# V3s.net
KiCad netlist of a schematic drawn in Altium Designer
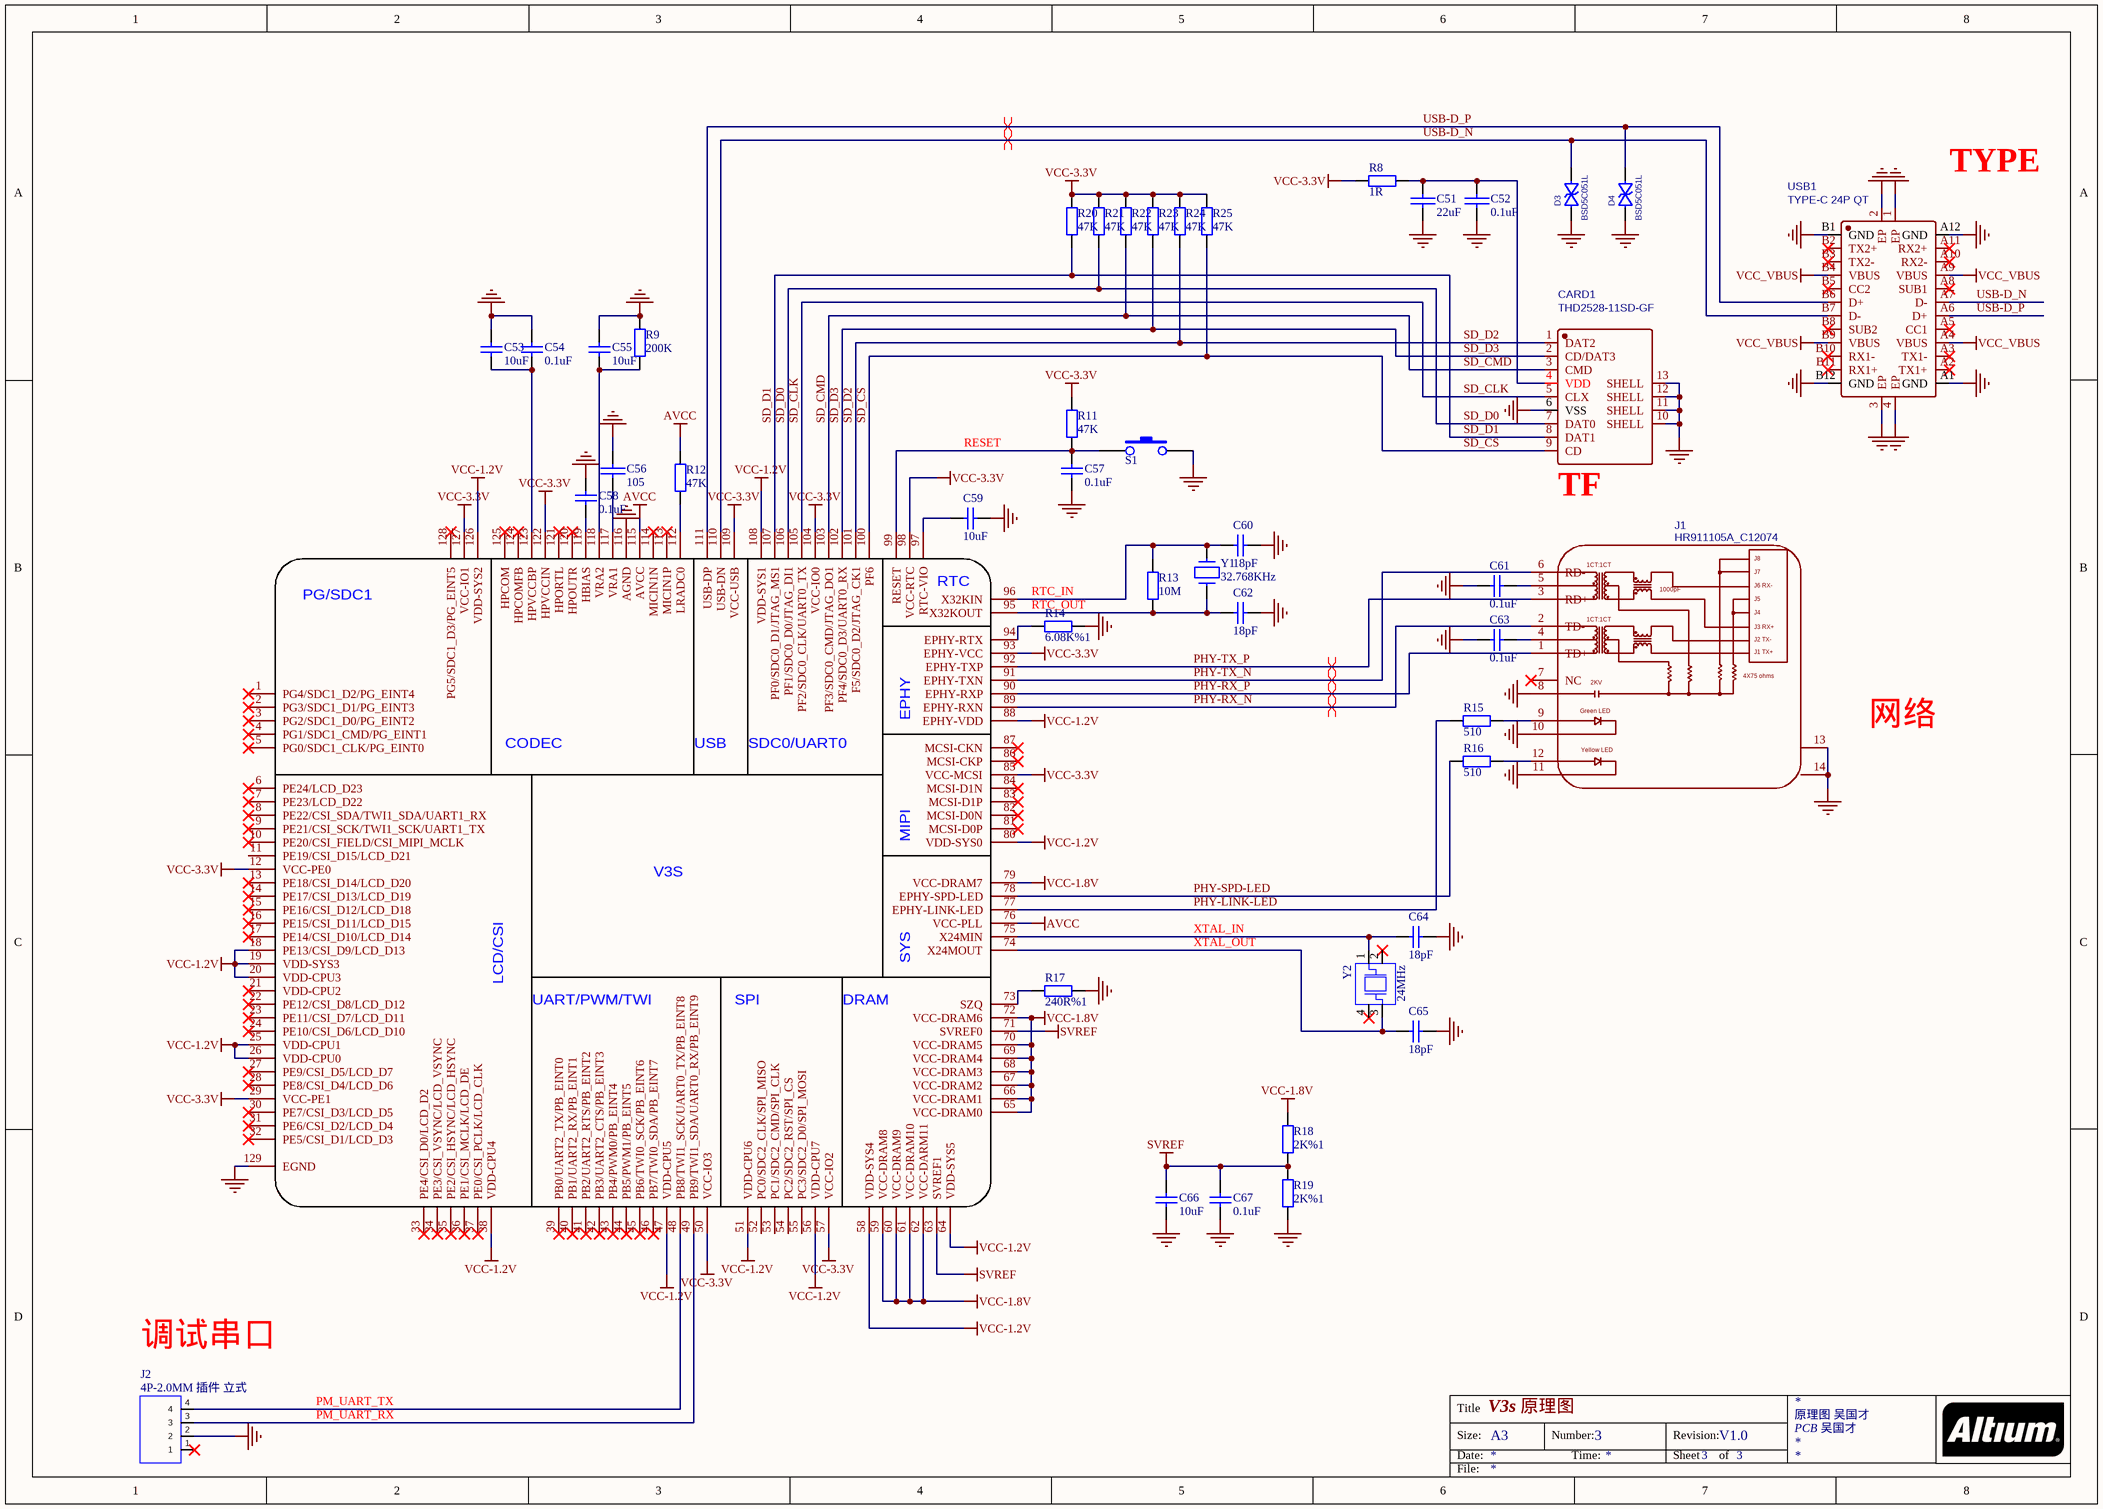
[diagram p0: V3s.SchDoc]

(export (version "E")
  (design (tool "Eeschema 10.0.6"))
  (components
    (comp (ref "C51")
      (value "22uF")
      (footprint "0805_C")
      (description "贴片电容")
      (libsource (lib "*") (part "CAP"))
    )
    (comp (ref "C52")
      (value "0.1uF")
      (footprint "0402_C")
      (description "贴片电容")
      (libsource (lib "*") (part "CAP"))
    )
    (comp (ref "C53")
      (value "10uF")
      (footprint "0603_C")
      (description "贴片电容")
      (libsource (lib "LSD") (part "CAP-SMD"))
    )
    (comp (ref "C54")
      (value "0.1uF")
      (footprint "0402_C")
      (description "贴片电容")
      (libsource (lib "LSD") (part "CAP-SMD"))
    )
    (comp (ref "C55")
      (value "10uF")
      (footprint "0603_C")
      (description "贴片电容")
      (libsource (lib "LSD") (part "CAP-SMD"))
    )
    (comp (ref "C56")
      (value "105")
      (footprint "0402_C")
      (description "贴片电容")
      (libsource (lib "*") (part "CAP"))
    )
    (comp (ref "C57")
      (value "0.1uF")
      (footprint "0402_C")
      (description "贴片电容")
      (libsource (lib "LSD") (part "CAP-SMD"))
    )
    (comp (ref "C58")
      (value "0.1uF")
      (footprint "0402_C")
      (description "贴片电容")
      (libsource (lib "LSD") (part "CAP-SMD"))
    )
    (comp (ref "C59")
      (value "10uF")
      (footprint "0603_C")
      (description "贴片电容")
      (libsource (lib "LSD") (part "CAP-SMD"))
    )
    (comp (ref "C60")
      (value "18pF")
      (footprint "0402_C")
      (description "贴片电容")
      (libsource (lib "电容") (part "CAP-SMD"))
    )
    (comp (ref "C61")
      (value "0.1uF")
      (footprint "0603_C")
      (description "贴片电容")
      (libsource (lib "LSD") (part "CAP-SMD"))
    )
    (comp (ref "C62")
      (value "18pF")
      (footprint "0402_C")
      (description "贴片电容")
      (libsource (lib "电容") (part "CAP-SMD"))
    )
    (comp (ref "C63")
      (value "0.1uF")
      (footprint "0603_C")
      (description "贴片电容")
      (libsource (lib "LSD") (part "CAP-SMD"))
    )
    (comp (ref "C64")
      (value "18pF")
      (footprint "0402_C")
      (description "贴片电容")
      (libsource (lib "LSD") (part "CAP-SMD"))
    )
    (comp (ref "C65")
      (value "18pF")
      (footprint "0402_C")
      (description "贴片电容")
      (libsource (lib "LSD") (part "CAP-SMD"))
    )
    (comp (ref "C66")
      (value "10uF")
      (footprint "0603_C")
      (description "贴片电容")
      (libsource (lib "LSD") (part "CAP-SMD"))
    )
    (comp (ref "C67")
      (value "0.1uF")
      (footprint "0402_C")
      (description "贴片电容")
      (libsource (lib "LSD") (part "CAP-SMD"))
    )
    (comp (ref "CARD1")
      (value "THD2528-11SD-GF")
      (footprint "TF-CARD-14.5X14.75X1.85MM")
      (fields (field (name "BOM_SUPPLIER PART") "C283232") (field (name "CONTRIBUTOR") "LCSC"))
      (libsource (lib "altium-import") (part "root_0_THD2528-11SD-GF_"))
    )
    (comp (ref "D3") (value "BSD5C051L") (footprint "SOD-523") (libsource (lib "*") (part "DIODE_ESD")))
    (comp (ref "D4") (value "BSD5C051L") (footprint "SOD-523") (libsource (lib "*") (part "DIODE_ESD")))
    (comp (ref "J1")
      (value "HR911105A_C12074")
      (footprint "HR913550A")
      (fields (field (name "BOM_MANUFACTURER PART") "HR911105A") (field (name "BOM_SUPPLIER PART") "C12074"))
      (libsource (lib "altium-import") (part "root_0_HR911105A_C12074_"))
    )
    (comp (ref "J2")
      (value "4P-2.0MM 插件 立式")
      (footprint "Hole,4P=2.00MM")
      (description "插件-立式插座")
      (fields (field (name "SOURCE_PATH") "E:\\JIANG\\二代产品开发资料\\设计参考\\A20CORNEL\\LIBRARY1.OLB"))
      (libsource (lib "*") (part "CON-4P"))
    )
    (comp (ref "R8")
      (value "1R")
      (footprint "0402_R")
      (description "贴片电阻")
      (libsource (lib "") (part "Res2_2"))
    )
    (comp (ref "R9")
      (value "200K")
      (footprint "0402_R")
      (description "贴片电阻")
      (libsource (lib "") (part "Res2_3"))
    )
    (comp (ref "R11")
      (value "47K")
      (footprint "0402_R")
      (description "贴片电阻")
      (libsource (lib "*") (part "Res2"))
    )
    (comp (ref "R12")
      (value "47K")
      (footprint "0402_R")
      (description "贴片电阻")
      (libsource (lib "*") (part "Res2"))
    )
    (comp (ref "R13")
      (value "10M")
      (footprint "0402_R")
      (description "贴片电阻")
      (libsource (lib "") (part "Res2_2"))
    )
    (comp (ref "R14")
      (value "6.08K%1")
      (footprint "0402_R")
      (description "贴片电阻")
      (libsource (lib "") (part "Res2_2"))
    )
    (comp (ref "R15")
      (value "510")
      (footprint "0402_R")
      (description "贴片电阻")
      (libsource (lib "") (part "Res2_1"))
    )
    (comp (ref "R16")
      (value "510")
      (footprint "0402_R")
      (description "贴片电阻")
      (libsource (lib "") (part "Res2_1"))
    )
    (comp (ref "R17")
      (value "240R%1")
      (footprint "0402_R")
      (description "贴片电阻")
      (libsource (lib "") (part "Res2_2"))
    )
    (comp (ref "R18")
      (value "2K%1")
      (footprint "0402_R")
      (description "贴片电阻")
      (libsource (lib "*") (part "Res2"))
    )
    (comp (ref "R19")
      (value "2K%1")
      (footprint "0402_R")
      (description "贴片电阻")
      (libsource (lib "*") (part "Res2"))
    )
    (comp (ref "R20")
      (value "47K")
      (footprint "0402_R")
      (description "贴片电阻")
      (libsource (lib "*") (part "Res2"))
    )
    (comp (ref "R21")
      (value "47K")
      (footprint "0402_R")
      (description "贴片电阻")
      (libsource (lib "*") (part "Res2"))
    )
    (comp (ref "R22")
      (value "47K")
      (footprint "0402_R")
      (description "贴片电阻")
      (libsource (lib "*") (part "Res2"))
    )
    (comp (ref "R23")
      (value "47K")
      (footprint "0402_R")
      (description "贴片电阻")
      (libsource (lib "*") (part "Res2"))
    )
    (comp (ref "R24")
      (value "47K")
      (footprint "0402_R")
      (description "贴片电阻")
      (libsource (lib "*") (part "Res2"))
    )
    (comp (ref "R25")
      (value "47K")
      (footprint "0402_R")
      (description "贴片电阻")
      (libsource (lib "*") (part "Res2"))
    )
    (comp (ref "S1") (value "SW-PB_1") (footprint "KEY-3X6-SMD") (libsource (lib "Devices") (part "SW-PB_1")))
    (comp (ref "USB1")
      (value "TYPE-C 24P QT")
      (footprint "USB-C-SMD_TYPE-C-24P-QT")
      (description "C2681555 品牌： SHOU HAN(首韩)")
      (fields (field (name "BOM_SUPPLIER PART") "C2681555") (field (name "CONTRIBUTOR") "LCSC"))
      (libsource (lib "altium-import") (part "root_0_TYPE-C 24P QT_"))
    )
    (comp (ref "V1")
      (value "V3S")
      (footprint "QUAD128")
      (fields (field (name "CONTRIBUTOR") "cnicfhnui"))
      (libsource (lib "altium-import") (part "root_0_V3S_"))
    )
    (comp (ref "Y1")
      (value "32.768KHz")
      (footprint "SMD3215-2P")
      (description "时钟晶体 32.768kHz 12.5PF 20PPM")
      (libsource (lib "晶振") (part "CRYSTAL-C"))
    )
    (comp (ref "Y2")
      (value "24MHz")
      (footprint "SMD3225-4P")
      (description "贴片无源晶振")
      (libsource (lib "*") (part "CRYSTAL4P_2"))
    )
  )
  (nets
    (net (code "1") (name "/PHY-LINK-LED") (class "Default")
      (node (ref "R15") (pin "2") (pinfunction "2_2") (pintype "passive"))
      (node (ref "V1") (pin "77") (pinfunction "EPHY-LINK-LED_77") (pintype "passive"))
    )
    (net (code "2") (name "/PHY-RX_N") (class "Default")
      (node (ref "J1") (pin "2") (pinfunction "TD-_2") (pintype "passive"))
      (node (ref "V1") (pin "89") (pinfunction "EPHY-RXN_89") (pintype "passive"))
    )
    (net (code "3") (name "/PHY-RX_P") (class "Default")
      (node (ref "J1") (pin "1") (pinfunction "TD+_1") (pintype "passive"))
      (node (ref "V1") (pin "90") (pinfunction "EPHY-RXP_90") (pintype "passive"))
    )
    (net (code "4") (name "/PHY-SPD-LED") (class "Default")
      (node (ref "R16") (pin "2") (pinfunction "2_2") (pintype "passive"))
      (node (ref "V1") (pin "78") (pinfunction "EPHY-SPD-LED_78") (pintype "passive"))
    )
    (net (code "5") (name "/PHY-TX_N") (class "Default")
      (node (ref "J1") (pin "6") (pinfunction "RD-_6") (pintype "passive"))
      (node (ref "V1") (pin "91") (pinfunction "EPHY-TXN_91") (pintype "passive"))
    )
    (net (code "6") (name "/PHY-TX_P") (class "Default")
      (node (ref "J1") (pin "3") (pinfunction "RD+_3") (pintype "passive"))
      (node (ref "V1") (pin "92") (pinfunction "EPHY-TXP_92") (pintype "passive"))
    )
    (net (code "7") (name "/PM_UART_RX") (class "Default")
      (node (ref "J2") (pin "3") (pinfunction "3_3") (pintype "passive"))
      (node (ref "V1") (pin "49") (pinfunction "PB9/TWI1_SDA/UART0_RX/PB_EINT9_49") (pintype "passive"))
    )
    (net (code "8") (name "/PM_UART_TX") (class "Default")
      (node (ref "J2") (pin "4") (pinfunction "4_4") (pintype "passive"))
      (node (ref "V1") (pin "48") (pinfunction "PB8/TWI1_SCK/UART0_TX/PB_EINT8_48") (pintype "passive"))
    )
    (net (code "9") (name "/RESET") (class "Default")
      (node (ref "C57") (pin "1") (pintype "passive"))
      (node (ref "R11") (pin "2") (pinfunction "2_2") (pintype "passive"))
      (node (ref "S1") (pin "2") (pinfunction "2_2") (pintype "passive"))
      (node (ref "V1") (pin "99") (pinfunction "RESET_99") (pintype "passive"))
    )
    (net (code "10") (name "/RTC_IN") (class "Default")
      (node (ref "C60") (pin "1") (pintype "passive"))
      (node (ref "R13") (pin "2") (pinfunction "2_2") (pintype "passive"))
      (node (ref "V1") (pin "96") (pinfunction "X32KIN_96") (pintype "passive"))
      (node (ref "Y1") (pin "2") (pinfunction "2_2") (pintype "passive"))
    )
    (net (code "11") (name "/RTC_OUT") (class "Default")
      (node (ref "C62") (pin "1") (pintype "passive"))
      (node (ref "R13") (pin "1") (pinfunction "1_1") (pintype "passive"))
      (node (ref "V1") (pin "95") (pinfunction "X32KOUT_95") (pintype "passive"))
      (node (ref "Y1") (pin "1") (pinfunction "1_1") (pintype "passive"))
    )
    (net (code "12") (name "/SD_CLK") (class "Default")
      (node (ref "CARD1") (pin "5") (pinfunction "CLX_5") (pintype "passive"))
      (node (ref "V1") (pin "105") (pinfunction "PF2/SDC0_CLK/UART0_TX_105") (pintype "passive"))
    )
    (net (code "13") (name "/SD_CMD") (class "Default")
      (node (ref "CARD1") (pin "3") (pinfunction "CMD_3") (pintype "passive"))
      (node (ref "R22") (pin "2") (pinfunction "2_2") (pintype "passive"))
      (node (ref "V1") (pin "103") (pinfunction "PF3/SDC0_CMD/JTAG_DO1_103") (pintype "passive"))
    )
    (net (code "14") (name "/SD_CS") (class "Default")
      (node (ref "CARD1") (pin "9") (pinfunction "CD_9") (pintype "passive"))
      (node (ref "R25") (pin "2") (pinfunction "2_2") (pintype "passive"))
      (node (ref "V1") (pin "100") (pinfunction "PF6_100") (pintype "passive"))
    )
    (net (code "15") (name "/SD_D0") (class "Default")
      (node (ref "CARD1") (pin "7") (pinfunction "DAT0_7") (pintype "passive"))
      (node (ref "R21") (pin "2") (pinfunction "2_2") (pintype "passive"))
      (node (ref "V1") (pin "106") (pinfunction "PF1/SDC0_D0/JTAG_DI1_106") (pintype "passive"))
    )
    (net (code "16") (name "/SD_D1") (class "Default")
      (node (ref "CARD1") (pin "8") (pinfunction "DAT1_8") (pintype "passive"))
      (node (ref "R20") (pin "2") (pinfunction "2_2") (pintype "passive"))
      (node (ref "V1") (pin "107") (pinfunction "PF0/SDC0_D1/JTAG_MS1_107") (pintype "passive"))
    )
    (net (code "17") (name "/SD_D2") (class "Default")
      (node (ref "CARD1") (pin "1") (pinfunction "DAT2_1") (pintype "passive"))
      (node (ref "R24") (pin "2") (pinfunction "2_2") (pintype "passive"))
      (node (ref "V1") (pin "101") (pinfunction "F5/SDC0_D2/JTAG_CK1_101") (pintype "passive"))
    )
    (net (code "18") (name "/SD_D3") (class "Default")
      (node (ref "CARD1") (pin "2") (pinfunction "CD/DAT3_2") (pintype "passive"))
      (node (ref "R23") (pin "2") (pinfunction "2_2") (pintype "passive"))
      (node (ref "V1") (pin "102") (pinfunction "PF4/SDC0_D3/UART0_RX_102") (pintype "passive"))
    )
    (net (code "19") (name "/USB-D_N") (class "Default")
      (node (ref "D3") (pin "2") (pinfunction "2_2") (pintype "passive"))
      (node (ref "USB1") (pin "A7") (pinfunction "D-_A7") (pintype "passive"))
      (node (ref "USB1") (pin "B7") (pinfunction "D-_B7") (pintype "passive"))
      (node (ref "V1") (pin "110") (pinfunction "USB-DN_110") (pintype "passive"))
    )
    (net (code "20") (name "/USB-D_P") (class "Default")
      (node (ref "D4") (pin "2") (pinfunction "2_2") (pintype "passive"))
      (node (ref "USB1") (pin "A6") (pinfunction "D+_A6") (pintype "passive"))
      (node (ref "USB1") (pin "B6") (pinfunction "D+_B6") (pintype "passive"))
      (node (ref "V1") (pin "111") (pinfunction "USB-DP_111") (pintype "passive"))
    )
    (net (code "21") (name "/XTAL_IN") (class "Default")
      (node (ref "C64") (pin "2") (pintype "passive"))
      (node (ref "V1") (pin "75") (pinfunction "X24MIN_75") (pintype "passive"))
      (node (ref "Y2") (pin "1") (pinfunction "CIN_1") (pintype "passive"))
    )
    (net (code "22") (name "/XTAL_OUT") (class "Default")
      (node (ref "C65") (pin "2") (pintype "passive"))
      (node (ref "V1") (pin "74") (pinfunction "X24MOUT_74") (pintype "passive"))
      (node (ref "Y2") (pin "3") (pinfunction "COUT_3") (pintype "passive"))
    )
    (net (code "23") (name "AVCC") (class "Default")
      (node (ref "R12") (pin "1") (pinfunction "1_1") (pintype "passive"))
      (node (ref "V1") (pin "115") (pinfunction "AVCC_115") (pintype "passive"))
      (node (ref "V1") (pin "76") (pinfunction "VCC-PLL_76") (pintype "passive"))
    )
    (net (code "24") (name "GND") (class "Default")
      (node (ref "C51") (pin "1") (pintype "passive"))
      (node (ref "C52") (pin "1") (pintype "passive"))
      (node (ref "C53") (pin "2") (pintype "passive"))
      (node (ref "C54") (pin "1") (pintype "passive"))
      (node (ref "C55") (pin "2") (pintype "passive"))
      (node (ref "C56") (pin "2") (pintype "passive"))
      (node (ref "C57") (pin "2") (pintype "passive"))
      (node (ref "C58") (pin "1") (pintype "passive"))
      (node (ref "C59") (pin "2") (pintype "passive"))
      (node (ref "C60") (pin "2") (pintype "passive"))
      (node (ref "C61") (pin "2") (pintype "passive"))
      (node (ref "C62") (pin "2") (pintype "passive"))
      (node (ref "C63") (pin "2") (pintype "passive"))
      (node (ref "C64") (pin "1") (pintype "passive"))
      (node (ref "C65") (pin "1") (pintype "passive"))
      (node (ref "C66") (pin "2") (pintype "passive"))
      (node (ref "C67") (pin "2") (pintype "passive"))
      (node (ref "CARD1") (pin "10") (pinfunction "SHELL_10") (pintype "passive"))
      (node (ref "CARD1") (pin "11") (pinfunction "SHELL_11") (pintype "passive"))
      (node (ref "CARD1") (pin "12") (pinfunction "SHELL_12") (pintype "passive"))
      (node (ref "CARD1") (pin "13") (pinfunction "SHELL_13") (pintype "passive"))
      (node (ref "CARD1") (pin "6") (pinfunction "VSS_6") (pintype "passive"))
      (node (ref "D3") (pin "1") (pinfunction "1_1") (pintype "passive"))
      (node (ref "D4") (pin "1") (pinfunction "1_1") (pintype "passive"))
      (node (ref "J1") (pin "10") (pinfunction "10_10") (pintype "passive"))
      (node (ref "J1") (pin "11") (pinfunction "11_11") (pintype "passive"))
      (node (ref "J1") (pin "13") (pinfunction "SH1_13") (pintype "passive"))
      (node (ref "J1") (pin "14") (pinfunction "SH2_14") (pintype "passive"))
      (node (ref "J1") (pin "8") (pinfunction "CHS_GND_8") (pintype "passive"))
      (node (ref "J2") (pin "2") (pinfunction "2_2") (pintype "passive"))
      (node (ref "R14") (pin "2") (pinfunction "2_2") (pintype "passive"))
      (node (ref "R17") (pin "2") (pinfunction "2_2") (pintype "passive"))
      (node (ref "R19") (pin "2") (pinfunction "2_2") (pintype "passive"))
      (node (ref "R9") (pin "2") (pinfunction "2_2") (pintype "passive"))
      (node (ref "S1") (pin "1") (pinfunction "1_1") (pintype "passive"))
      (node (ref "USB1") (pin "1") (pinfunction "EP_1") (pintype "passive"))
      (node (ref "USB1") (pin "2") (pinfunction "EP_2") (pintype "passive"))
      (node (ref "USB1") (pin "3") (pinfunction "EP_3") (pintype "passive"))
      (node (ref "USB1") (pin "4") (pinfunction "EP_4") (pintype "passive"))
      (node (ref "USB1") (pin "A1") (pinfunction "GND_A1") (pintype "passive"))
      (node (ref "USB1") (pin "A12") (pinfunction "GND_A12") (pintype "passive"))
      (node (ref "USB1") (pin "B1") (pinfunction "GND_B1") (pintype "passive"))
      (node (ref "USB1") (pin "B12") (pinfunction "GND_B12") (pintype "passive"))
      (node (ref "V1") (pin "116") (pinfunction "AGND_116") (pintype "passive"))
      (node (ref "V1") (pin "129") (pinfunction "EGND_129") (pintype "passive"))
    )
    (net (code "25") (name "Net-(C61-Pad1)") (class "Default")
      (node (ref "C61") (pin "1") (pintype "passive"))
      (node (ref "J1") (pin "5") (pinfunction "5_5") (pintype "passive"))
    )
    (net (code "26") (name "Net-(C63-Pad1)") (class "Default")
      (node (ref "C63") (pin "1") (pintype "passive"))
      (node (ref "J1") (pin "4") (pinfunction "4_4") (pintype "passive"))
    )
    (net (code "27") (name "Net-(CARD1-VDD)") (class "Default")
      (node (ref "C51") (pin "2") (pintype "passive"))
      (node (ref "C52") (pin "2") (pintype "passive"))
      (node (ref "CARD1") (pin "4") (pinfunction "VDD_4") (pintype "passive"))
      (node (ref "R8") (pin "2") (pinfunction "2_2") (pintype "passive"))
    )
    (net (code "28") (name "Net-(J1-Pad9)") (class "Default")
      (node (ref "J1") (pin "9") (pinfunction "9_9") (pintype "passive"))
      (node (ref "R15") (pin "1") (pinfunction "1_1") (pintype "passive"))
    )
    (net (code "29") (name "Net-(J1-Pad12)") (class "Default")
      (node (ref "J1") (pin "12") (pinfunction "12_12") (pintype "passive"))
      (node (ref "R16") (pin "1") (pinfunction "1_1") (pintype "passive"))
    )
    (net (code "30") (name "Net-(V1-EPHY-RTX)") (class "Default")
      (node (ref "R14") (pin "1") (pinfunction "1_1") (pintype "passive"))
      (node (ref "V1") (pin "94") (pinfunction "EPHY-RTX_94") (pintype "passive"))
    )
    (net (code "31") (name "Net-(V1-HBIAS)") (class "Default")
      (node (ref "C58") (pin "2") (pintype "passive"))
      (node (ref "V1") (pin "119") (pinfunction "HBIAS_119") (pintype "passive"))
    )
    (net (code "32") (name "Net-(V1-HPVCCBP)") (class "Default")
      (node (ref "C53") (pin "1") (pintype "passive"))
      (node (ref "C54") (pin "2") (pintype "passive"))
      (node (ref "V1") (pin "123") (pinfunction "HPVCCBP_123") (pintype "passive"))
    )
    (net (code "33") (name "Net-(V1-LRADC0)") (class "Default")
      (node (ref "R12") (pin "2") (pinfunction "2_2") (pintype "passive"))
      (node (ref "V1") (pin "112") (pinfunction "LRADC0_112") (pintype "passive"))
    )
    (net (code "34") (name "Net-(V1-RTC-VIO)") (class "Default")
      (node (ref "C59") (pin "1") (pintype "passive"))
      (node (ref "V1") (pin "97") (pinfunction "RTC-VIO_97") (pintype "passive"))
    )
    (net (code "35") (name "Net-(V1-SZQ)") (class "Default")
      (node (ref "R17") (pin "1") (pinfunction "1_1") (pintype "passive"))
      (node (ref "V1") (pin "73") (pinfunction "SZQ_73") (pintype "passive"))
    )
    (net (code "36") (name "Net-(V1-VRA1)") (class "Default")
      (node (ref "C56") (pin "1") (pintype "passive"))
      (node (ref "V1") (pin "117") (pinfunction "VRA1_117") (pintype "passive"))
    )
    (net (code "37") (name "Net-(V1-VRA2)") (class "Default")
      (node (ref "C55") (pin "1") (pintype "passive"))
      (node (ref "R9") (pin "1") (pinfunction "1_1") (pintype "passive"))
      (node (ref "V1") (pin "118") (pinfunction "VRA2_118") (pintype "passive"))
    )
    (net (code "38") (name "SVREF") (class "Default")
      (node (ref "C66") (pin "1") (pintype "passive"))
      (node (ref "C67") (pin "1") (pintype "passive"))
      (node (ref "R18") (pin "2") (pinfunction "2_2") (pintype "passive"))
      (node (ref "R19") (pin "1") (pinfunction "1_1") (pintype "passive"))
      (node (ref "V1") (pin "63") (pinfunction "SVREF1_63") (pintype "passive"))
      (node (ref "V1") (pin "71") (pinfunction "SVREF0_71") (pintype "passive"))
    )
    (net (code "39") (name "VCC-1.2V") (class "Default")
      (node (ref "V1") (pin "108") (pinfunction "VDD-SYS1_108") (pintype "passive"))
      (node (ref "V1") (pin "126") (pinfunction "VDD-SYS2_126") (pintype "passive"))
      (node (ref "V1") (pin "18") (pinfunction "PE13/CSI_D9/LCD_D13_18") (pintype "passive"))
      (node (ref "V1") (pin "19") (pinfunction "VDD-SYS3_19") (pintype "passive"))
      (node (ref "V1") (pin "20") (pinfunction "VDD-CPU3_20") (pintype "passive"))
      (node (ref "V1") (pin "25") (pinfunction "VDD-CPU1_25") (pintype "passive"))
      (node (ref "V1") (pin "26") (pinfunction "VDD-CPU0_26") (pintype "passive"))
      (node (ref "V1") (pin "38") (pinfunction "VDD-CPU4_38") (pintype "passive"))
      (node (ref "V1") (pin "47") (pinfunction "VDD-CPU5_47") (pintype "passive"))
      (node (ref "V1") (pin "51") (pinfunction "VDD-CPU6_51") (pintype "passive"))
      (node (ref "V1") (pin "56") (pinfunction "VDD-CPU7_56") (pintype "passive"))
      (node (ref "V1") (pin "58") (pinfunction "VDD-SYS4_58") (pintype "passive"))
      (node (ref "V1") (pin "64") (pinfunction "VDD-SYS5_64") (pintype "passive"))
      (node (ref "V1") (pin "80") (pinfunction "VDD-SYS0_80") (pintype "passive"))
      (node (ref "V1") (pin "88") (pinfunction "EPHY-VDD_88") (pintype "passive"))
    )
    (net (code "40") (name "VCC-1.8V") (class "Default")
      (node (ref "R18") (pin "1") (pinfunction "1_1") (pintype "passive"))
      (node (ref "V1") (pin "59") (pinfunction "VCC-DRAM8_59") (pintype "passive"))
      (node (ref "V1") (pin "60") (pinfunction "VCC-DRAM9_60") (pintype "passive"))
      (node (ref "V1") (pin "61") (pinfunction "VCC-DRAM10_61") (pintype "passive"))
      (node (ref "V1") (pin "62") (pinfunction "VCC-DARM11_62") (pintype "passive"))
      (node (ref "V1") (pin "65") (pinfunction "VCC-DRAM0_65") (pintype "passive"))
      (node (ref "V1") (pin "66") (pinfunction "VCC-DRAM1_66") (pintype "passive"))
      (node (ref "V1") (pin "67") (pinfunction "VCC-DRAM2_67") (pintype "passive"))
      (node (ref "V1") (pin "68") (pinfunction "VCC-DRAM3_68") (pintype "passive"))
      (node (ref "V1") (pin "69") (pinfunction "VCC-DRAM4_69") (pintype "passive"))
      (node (ref "V1") (pin "70") (pinfunction "VCC-DRAM5_70") (pintype "passive"))
      (node (ref "V1") (pin "72") (pinfunction "VCC-DRAM6_72") (pintype "passive"))
      (node (ref "V1") (pin "79") (pinfunction "VCC-DRAM7_79") (pintype "passive"))
    )
    (net (code "41") (name "VCC-3.3V") (class "Default")
      (node (ref "R11") (pin "1") (pinfunction "1_1") (pintype "passive"))
      (node (ref "R20") (pin "1") (pinfunction "1_1") (pintype "passive"))
      (node (ref "R21") (pin "1") (pinfunction "1_1") (pintype "passive"))
      (node (ref "R22") (pin "1") (pinfunction "1_1") (pintype "passive"))
      (node (ref "R23") (pin "1") (pinfunction "1_1") (pintype "passive"))
      (node (ref "R24") (pin "1") (pinfunction "1_1") (pintype "passive"))
      (node (ref "R25") (pin "1") (pinfunction "1_1") (pintype "passive"))
      (node (ref "R8") (pin "1") (pinfunction "1_1") (pintype "passive"))
      (node (ref "V1") (pin "104") (pinfunction "VCC-IO0_104") (pintype "passive"))
      (node (ref "V1") (pin "109") (pinfunction "VCC-USB_109") (pintype "passive"))
      (node (ref "V1") (pin "12") (pinfunction "VCC-PE0_12") (pintype "passive"))
      (node (ref "V1") (pin "122") (pinfunction "HPVCCIN_122") (pintype "passive"))
      (node (ref "V1") (pin "127") (pinfunction "VCC-IO1_127") (pintype "passive"))
      (node (ref "V1") (pin "29") (pinfunction "VCC-PE1_29") (pintype "passive"))
      (node (ref "V1") (pin "50") (pinfunction "VCC-IO3_50") (pintype "passive"))
      (node (ref "V1") (pin "57") (pinfunction "VCC-IO2_57") (pintype "passive"))
      (node (ref "V1") (pin "85") (pinfunction "VCC-MCSI_85") (pintype "passive"))
      (node (ref "V1") (pin "93") (pinfunction "EPHY-VCC_93") (pintype "passive"))
      (node (ref "V1") (pin "98") (pinfunction "VCC-RTC_98") (pintype "passive"))
    )
    (net (code "42") (name "VCC_VBUS") (class "Default")
      (node (ref "USB1") (pin "A4") (pinfunction "VBUS_A4") (pintype "passive"))
      (node (ref "USB1") (pin "A9") (pinfunction "VBUS_A9") (pintype "passive"))
      (node (ref "USB1") (pin "B4") (pinfunction "VBUS_B4") (pintype "passive"))
      (node (ref "USB1") (pin "B9") (pinfunction "VBUS_B9") (pintype "passive"))
    )
    (net (code "43") (name "unconnected-(J1-NC-Pad7)") (class "Default")
      (node (ref "J1") (pin "7") (pinfunction "NC_7") (pintype "passive+no_connect"))
    )
    (net (code "44") (name "unconnected-(J2-Pad1)") (class "Default")
      (node (ref "J2") (pin "1") (pinfunction "1_1") (pintype "passive+no_connect"))
    )
    (net (code "45") (name "unconnected-(USB1-CC1-PadA5)") (class "Default")
      (node (ref "USB1") (pin "A5") (pinfunction "CC1_A5") (pintype "passive+no_connect"))
    )
    (net (code "46") (name "unconnected-(USB1-CC2-PadB5)") (class "Default")
      (node (ref "USB1") (pin "B5") (pinfunction "CC2_B5") (pintype "passive+no_connect"))
    )
    (net (code "47") (name "unconnected-(USB1-RX1+-PadB11)") (class "Default")
      (node (ref "USB1") (pin "B11") (pinfunction "RX1+_B11") (pintype "passive+no_connect"))
    )
    (net (code "48") (name "unconnected-(USB1-RX1--PadB10)") (class "Default")
      (node (ref "USB1") (pin "B10") (pinfunction "RX1-_B10") (pintype "passive+no_connect"))
    )
    (net (code "49") (name "unconnected-(USB1-RX2+-PadA11)") (class "Default")
      (node (ref "USB1") (pin "A11") (pinfunction "RX2+_A11") (pintype "passive+no_connect"))
    )
    (net (code "50") (name "unconnected-(USB1-RX2--PadA10)") (class "Default")
      (node (ref "USB1") (pin "A10") (pinfunction "RX2-_A10") (pintype "passive+no_connect"))
    )
    (net (code "51") (name "unconnected-(USB1-SUB1-PadA8)") (class "Default")
      (node (ref "USB1") (pin "A8") (pinfunction "SUB1_A8") (pintype "passive+no_connect"))
    )
    (net (code "52") (name "unconnected-(USB1-SUB2-PadB8)") (class "Default")
      (node (ref "USB1") (pin "B8") (pinfunction "SUB2_B8") (pintype "passive+no_connect"))
    )
    (net (code "53") (name "unconnected-(USB1-TX1+-PadA2)") (class "Default")
      (node (ref "USB1") (pin "A2") (pinfunction "TX1+_A2") (pintype "passive+no_connect"))
    )
    (net (code "54") (name "unconnected-(USB1-TX1--PadA3)") (class "Default")
      (node (ref "USB1") (pin "A3") (pinfunction "TX1-_A3") (pintype "passive+no_connect"))
    )
    (net (code "55") (name "unconnected-(USB1-TX2+-PadB2)") (class "Default")
      (node (ref "USB1") (pin "B2") (pinfunction "TX2+_B2") (pintype "passive+no_connect"))
    )
    (net (code "56") (name "unconnected-(USB1-TX2--PadB3)") (class "Default")
      (node (ref "USB1") (pin "B3") (pinfunction "TX2-_B3") (pintype "passive+no_connect"))
    )
    (net (code "57") (name "unconnected-(V1-HPCOM-Pad125)") (class "Default")
      (node (ref "V1") (pin "125") (pinfunction "HPCOM_125") (pintype "passive+no_connect"))
    )
    (net (code "58") (name "unconnected-(V1-HPCOMFB-Pad124)") (class "Default")
      (node (ref "V1") (pin "124") (pinfunction "HPCOMFB_124") (pintype "passive+no_connect"))
    )
    (net (code "59") (name "unconnected-(V1-HPORTL-Pad121)") (class "Default")
      (node (ref "V1") (pin "121") (pinfunction "HPORTL_121") (pintype "passive+no_connect"))
    )
    (net (code "60") (name "unconnected-(V1-HPOUTR-Pad120)") (class "Default")
      (node (ref "V1") (pin "120") (pinfunction "HPOUTR_120") (pintype "passive+no_connect"))
    )
    (net (code "61") (name "unconnected-(V1-MCSI-CKN-Pad87)") (class "Default")
      (node (ref "V1") (pin "87") (pinfunction "MCSI-CKN_87") (pintype "passive+no_connect"))
    )
    (net (code "62") (name "unconnected-(V1-MCSI-CKP-Pad86)") (class "Default")
      (node (ref "V1") (pin "86") (pinfunction "MCSI-CKP_86") (pintype "passive+no_connect"))
    )
    (net (code "63") (name "unconnected-(V1-MCSI-D0N-Pad82)") (class "Default")
      (node (ref "V1") (pin "82") (pinfunction "MCSI-D0N_82") (pintype "passive+no_connect"))
    )
    (net (code "64") (name "unconnected-(V1-MCSI-D0P-Pad81)") (class "Default")
      (node (ref "V1") (pin "81") (pinfunction "MCSI-D0P_81") (pintype "passive+no_connect"))
    )
    (net (code "65") (name "unconnected-(V1-MCSI-D1N-Pad84)") (class "Default")
      (node (ref "V1") (pin "84") (pinfunction "MCSI-D1N_84") (pintype "passive+no_connect"))
    )
    (net (code "66") (name "unconnected-(V1-MCSI-D1P-Pad83)") (class "Default")
      (node (ref "V1") (pin "83") (pinfunction "MCSI-D1P_83") (pintype "passive+no_connect"))
    )
    (net (code "67") (name "unconnected-(V1-MICIN1N-Pad114)") (class "Default")
      (node (ref "V1") (pin "114") (pinfunction "MICIN1N_114") (pintype "passive+no_connect"))
    )
    (net (code "68") (name "unconnected-(V1-MICIN1P-Pad113)") (class "Default")
      (node (ref "V1") (pin "113") (pinfunction "MICIN1P_113") (pintype "passive+no_connect"))
    )
    (net (code "69") (name "unconnected-(V1-PB0{slash}UART2_TX{slash}PB_EINT0-Pad39)") (class "Default")
      (node (ref "V1") (pin "39") (pinfunction "PB0/UART2_TX/PB_EINT0_39") (pintype "passive+no_connect"))
    )
    (net (code "70") (name "unconnected-(V1-PB1{slash}UART2_RX{slash}PB_EINT1-Pad40)") (class "Default")
      (node (ref "V1") (pin "40") (pinfunction "PB1/UART2_RX/PB_EINT1_40") (pintype "passive+no_connect"))
    )
    (net (code "71") (name "unconnected-(V1-PB2{slash}UART2_RTS{slash}PB_EINT2-Pad41)") (class "Default")
      (node (ref "V1") (pin "41") (pinfunction "PB2/UART2_RTS/PB_EINT2_41") (pintype "passive+no_connect"))
    )
    (net (code "72") (name "unconnected-(V1-PB3{slash}UART2_CTS{slash}PB_EINT3-Pad42)") (class "Default")
      (node (ref "V1") (pin "42") (pinfunction "PB3/UART2_CTS/PB_EINT3_42") (pintype "passive+no_connect"))
    )
    (net (code "73") (name "unconnected-(V1-PB4{slash}PWM0{slash}PB_EINT4-Pad43)") (class "Default")
      (node (ref "V1") (pin "43") (pinfunction "PB4/PWM0/PB_EINT4_43") (pintype "passive+no_connect"))
    )
    (net (code "74") (name "unconnected-(V1-PB5{slash}PWM1{slash}PB_EINT5-Pad44)") (class "Default")
      (node (ref "V1") (pin "44") (pinfunction "PB5/PWM1/PB_EINT5_44") (pintype "passive+no_connect"))
    )
    (net (code "75") (name "unconnected-(V1-PB6{slash}TWI0_SCK{slash}PB_EINT6-Pad45)") (class "Default")
      (node (ref "V1") (pin "45") (pinfunction "PB6/TWI0_SCK/PB_EINT6_45") (pintype "passive+no_connect"))
    )
    (net (code "76") (name "unconnected-(V1-PB7{slash}TWI0_SDA{slash}PB_EINT7-Pad46)") (class "Default")
      (node (ref "V1") (pin "46") (pinfunction "PB7/TWI0_SDA/PB_EINT7_46") (pintype "passive+no_connect"))
    )
    (net (code "77") (name "unconnected-(V1-PC0{slash}SDC2_CLK{slash}SPI_MISO-Pad52)") (class "Default")
      (node (ref "V1") (pin "52") (pinfunction "PC0/SDC2_CLK/SPI_MISO_52") (pintype "passive"))
    )
    (net (code "78") (name "unconnected-(V1-PC1{slash}SDC2_CMD{slash}SPI_CLK-Pad53)") (class "Default")
      (node (ref "V1") (pin "53") (pinfunction "PC1/SDC2_CMD/SPI_CLK_53") (pintype "passive"))
    )
    (net (code "79") (name "unconnected-(V1-PC2{slash}SDC2_RST{slash}SPI_CS-Pad54)") (class "Default")
      (node (ref "V1") (pin "54") (pinfunction "PC2/SDC2_RST/SPI_CS_54") (pintype "passive"))
    )
    (net (code "80") (name "unconnected-(V1-PC3{slash}SDC2_D0{slash}SPI_MOSI-Pad55)") (class "Default")
      (node (ref "V1") (pin "55") (pinfunction "PC3/SDC2_D0/SPI_MOSI_55") (pintype "passive"))
    )
    (net (code "81") (name "unconnected-(V1-PE0{slash}CSI_PCLK{slash}LCD_CLK-Pad37)") (class "Default")
      (node (ref "V1") (pin "37") (pinfunction "PE0/CSI_PCLK/LCD_CLK_37") (pintype "passive+no_connect"))
    )
    (net (code "82") (name "unconnected-(V1-PE1{slash}CSI_MCLK{slash}LCD_DE-Pad36)") (class "Default")
      (node (ref "V1") (pin "36") (pinfunction "PE1/CSI_MCLK/LCD_DE_36") (pintype "passive+no_connect"))
    )
    (net (code "83") (name "unconnected-(V1-PE2{slash}CSI_HSYNC{slash}LCD_HSYNC-Pad35)") (class "Default")
      (node (ref "V1") (pin "35") (pinfunction "PE2/CSI_HSYNC/LCD_HSYNC_35") (pintype "passive+no_connect"))
    )
    (net (code "84") (name "unconnected-(V1-PE3{slash}CSI_VSYNC{slash}LCD_VSYNC-Pad34)") (class "Default")
      (node (ref "V1") (pin "34") (pinfunction "PE3/CSI_VSYNC/LCD_VSYNC_34") (pintype "passive+no_connect"))
    )
    (net (code "85") (name "unconnected-(V1-PE4{slash}CSI_D0{slash}LCD_D2-Pad33)") (class "Default")
      (node (ref "V1") (pin "33") (pinfunction "PE4/CSI_D0/LCD_D2_33") (pintype "passive+no_connect"))
    )
    (net (code "86") (name "unconnected-(V1-PE5{slash}CSI_D1{slash}LCD_D3-Pad32)") (class "Default")
      (node (ref "V1") (pin "32") (pinfunction "PE5/CSI_D1/LCD_D3_32") (pintype "passive+no_connect"))
    )
    (net (code "87") (name "unconnected-(V1-PE6{slash}CSI_D2{slash}LCD_D4-Pad31)") (class "Default")
      (node (ref "V1") (pin "31") (pinfunction "PE6/CSI_D2/LCD_D4_31") (pintype "passive+no_connect"))
    )
    (net (code "88") (name "unconnected-(V1-PE7{slash}CSI_D3{slash}LCD_D5-Pad30)") (class "Default")
      (node (ref "V1") (pin "30") (pinfunction "PE7/CSI_D3/LCD_D5_30") (pintype "passive+no_connect"))
    )
    (net (code "89") (name "unconnected-(V1-PE8{slash}CSI_D4{slash}LCD_D6-Pad28)") (class "Default")
      (node (ref "V1") (pin "28") (pinfunction "PE8/CSI_D4/LCD_D6_28") (pintype "passive+no_connect"))
    )
    (net (code "90") (name "unconnected-(V1-PE9{slash}CSI_D5{slash}LCD_D7-Pad27)") (class "Default")
      (node (ref "V1") (pin "27") (pinfunction "PE9/CSI_D5/LCD_D7_27") (pintype "passive+no_connect"))
    )
    (net (code "91") (name "unconnected-(V1-PE10{slash}CSI_D6{slash}LCD_D10-Pad24)") (class "Default")
      (node (ref "V1") (pin "24") (pinfunction "PE10/CSI_D6/LCD_D10_24") (pintype "passive+no_connect"))
    )
    (net (code "92") (name "unconnected-(V1-PE11{slash}CSI_D7{slash}LCD_D11-Pad23)") (class "Default")
      (node (ref "V1") (pin "23") (pinfunction "PE11/CSI_D7/LCD_D11_23") (pintype "passive+no_connect"))
    )
    (net (code "93") (name "unconnected-(V1-PE12{slash}CSI_D8{slash}LCD_D12-Pad22)") (class "Default")
      (node (ref "V1") (pin "22") (pinfunction "PE12/CSI_D8/LCD_D12_22") (pintype "passive+no_connect"))
    )
    (net (code "94") (name "unconnected-(V1-PE14{slash}CSI_D10{slash}LCD_D14-Pad17)") (class "Default")
      (node (ref "V1") (pin "17") (pinfunction "PE14/CSI_D10/LCD_D14_17") (pintype "passive+no_connect"))
    )
    (net (code "95") (name "unconnected-(V1-PE15{slash}CSI_D11{slash}LCD_D15-Pad16)") (class "Default")
      (node (ref "V1") (pin "16") (pinfunction "PE15/CSI_D11/LCD_D15_16") (pintype "passive+no_connect"))
    )
    (net (code "96") (name "unconnected-(V1-PE16{slash}CSI_D12{slash}LCD_D18-Pad15)") (class "Default")
      (node (ref "V1") (pin "15") (pinfunction "PE16/CSI_D12/LCD_D18_15") (pintype "passive+no_connect"))
    )
    (net (code "97") (name "unconnected-(V1-PE17{slash}CSI_D13{slash}LCD_D19-Pad14)") (class "Default")
      (node (ref "V1") (pin "14") (pinfunction "PE17/CSI_D13/LCD_D19_14") (pintype "passive+no_connect"))
    )
    (net (code "98") (name "unconnected-(V1-PE18{slash}CSI_D14{slash}LCD_D20-Pad13)") (class "Default")
      (node (ref "V1") (pin "13") (pinfunction "PE18/CSI_D14/LCD_D20_13") (pintype "passive+no_connect"))
    )
    (net (code "99") (name "unconnected-(V1-PE19{slash}CSI_D15{slash}LCD_D21-Pad11)") (class "Default")
      (node (ref "V1") (pin "11") (pinfunction "PE19/CSI_D15/LCD_D21_11") (pintype "passive"))
    )
    (net (code "100") (name "unconnected-(V1-PE20{slash}CSI_FIELD{slash}CSI_MIPI_MCLK-Pad10)") (class "Default")
      (node (ref "V1") (pin "10") (pinfunction "PE20/CSI_FIELD/CSI_MIPI_MCLK_10") (pintype "passive+no_connect"))
    )
    (net (code "101") (name "unconnected-(V1-PE21{slash}CSI_SCK{slash}TWI1_SCK{slash}UART1_TX-Pad9)") (class "Default")
      (node (ref "V1") (pin "9") (pinfunction "PE21/CSI_SCK/TWI1_SCK/UART1_TX_9") (pintype "passive+no_connect"))
    )
    (net (code "102") (name "unconnected-(V1-PE22{slash}CSI_SDA{slash}TWI1_SDA{slash}UART1_RX-Pad8)") (class "Default")
      (node (ref "V1") (pin "8") (pinfunction "PE22/CSI_SDA/TWI1_SDA/UART1_RX_8") (pintype "passive+no_connect"))
    )
    (net (code "103") (name "unconnected-(V1-PE23{slash}LCD_D22-Pad7)") (class "Default")
      (node (ref "V1") (pin "7") (pinfunction "PE23/LCD_D22_7") (pintype "passive+no_connect"))
    )
    (net (code "104") (name "unconnected-(V1-PE24{slash}LCD_D23-Pad6)") (class "Default")
      (node (ref "V1") (pin "6") (pinfunction "PE24/LCD_D23_6") (pintype "passive+no_connect"))
    )
    (net (code "105") (name "unconnected-(V1-PG0{slash}SDC1_CLK{slash}PG_EINT0-Pad5)") (class "Default")
      (node (ref "V1") (pin "5") (pinfunction "PG0/SDC1_CLK/PG_EINT0_5") (pintype "passive+no_connect"))
    )
    (net (code "106") (name "unconnected-(V1-PG1{slash}SDC1_CMD{slash}PG_EINT1-Pad4)") (class "Default")
      (node (ref "V1") (pin "4") (pinfunction "PG1/SDC1_CMD/PG_EINT1_4") (pintype "passive+no_connect"))
    )
    (net (code "107") (name "unconnected-(V1-PG2{slash}SDC1_D0{slash}PG_EINT2-Pad3)") (class "Default")
      (node (ref "V1") (pin "3") (pinfunction "PG2/SDC1_D0/PG_EINT2_3") (pintype "passive+no_connect"))
    )
    (net (code "108") (name "unconnected-(V1-PG3{slash}SDC1_D1{slash}PG_EINT3-Pad2)") (class "Default")
      (node (ref "V1") (pin "2") (pinfunction "PG3/SDC1_D1/PG_EINT3_2") (pintype "passive+no_connect"))
    )
    (net (code "109") (name "unconnected-(V1-PG4{slash}SDC1_D2{slash}PG_EINT4-Pad1)") (class "Default")
      (node (ref "V1") (pin "1") (pinfunction "PG4/SDC1_D2/PG_EINT4_1") (pintype "passive+no_connect"))
    )
    (net (code "110") (name "unconnected-(V1-PG5{slash}SDC1_D3{slash}PG_EINT5-Pad128)") (class "Default")
      (node (ref "V1") (pin "128") (pinfunction "PG5/SDC1_D3/PG_EINT5_128") (pintype "passive+no_connect"))
    )
    (net (code "111") (name "unconnected-(V1-VDD-CPU2-Pad21)") (class "Default")
      (node (ref "V1") (pin "21") (pinfunction "VDD-CPU2_21") (pintype "passive+no_connect"))
    )
    (net (code "112") (name "unconnected-(Y2-Pad2)") (class "Default")
      (node (ref "Y2") (pin "2") (pinfunction "2_2") (pintype "passive+no_connect"))
    )
    (net (code "113") (name "unconnected-(Y2-Pad4)") (class "Default")
      (node (ref "Y2") (pin "4") (pinfunction "4_4") (pintype "passive+no_connect"))
    )
  )
)
